# ECU_Dummy.net
KiCad netlist of a schematic drawn in Altium Designer
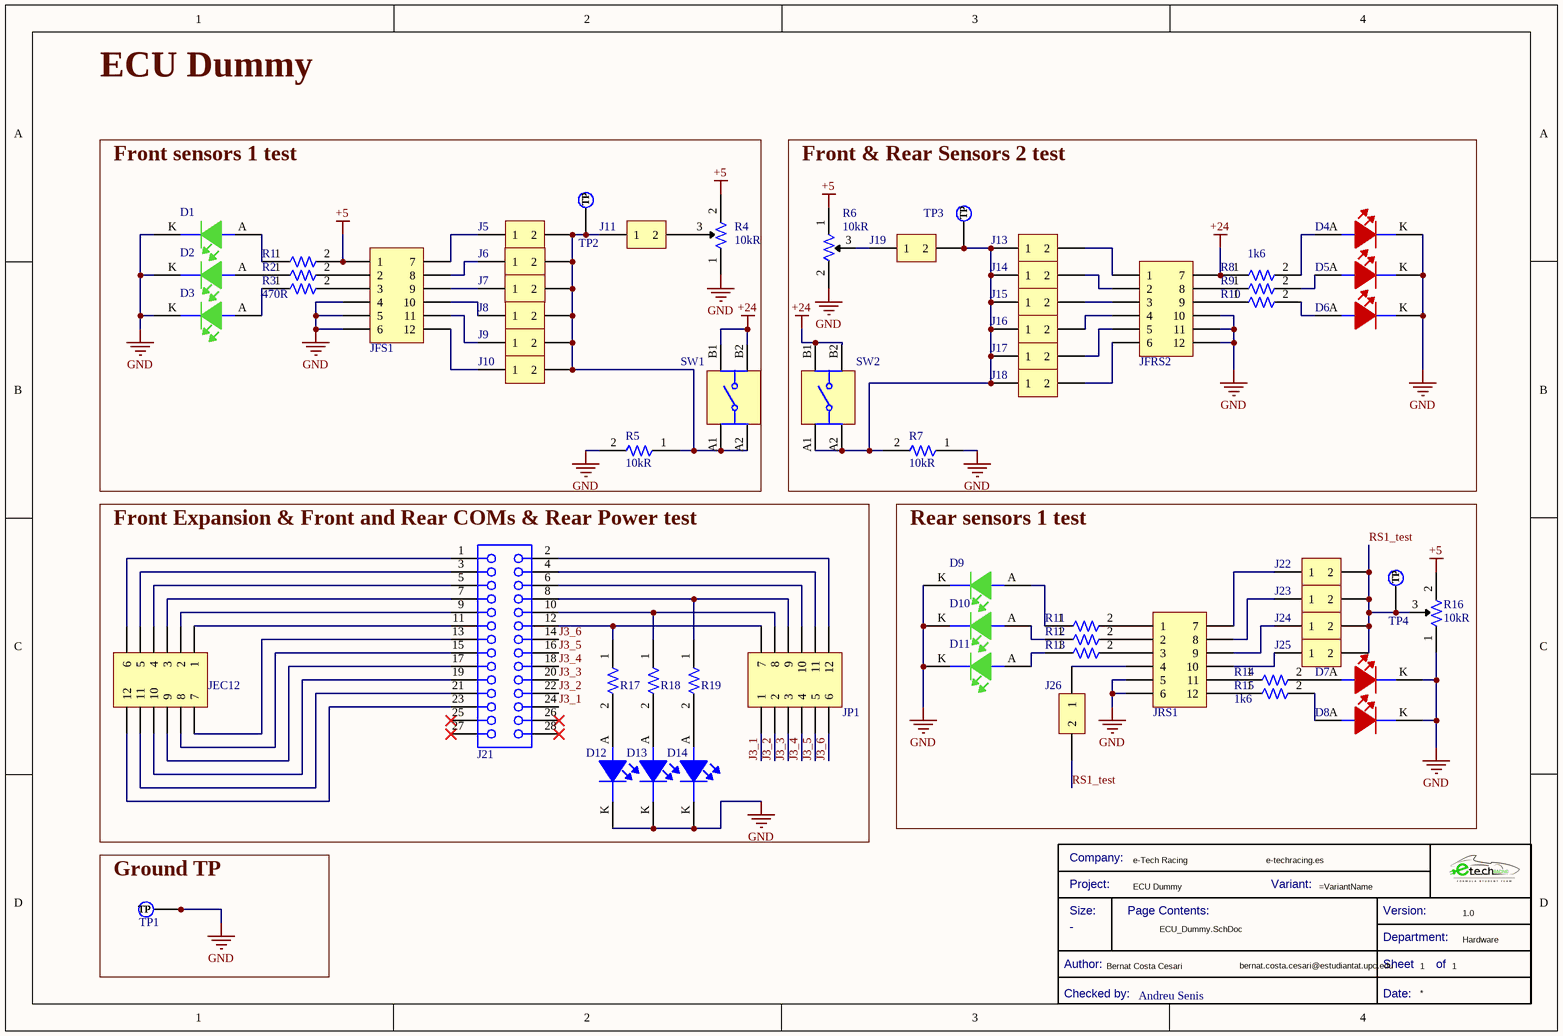
[diagram p0: ECU_Dummy.SchDoc]

(export (version "E")
  (design (tool "Eeschema 10.0.6"))
  (components
    (comp (ref "*")
      (value "Title Block_template")
      (description "Standard Title Block")
      (fields
        (field (name "SIZE") "-")
        (field (name ".CREATOR") "GP")
        (field (name ".PCBCHECK") "GP")
        (field (name ".SCHCHECK") "GP")
      )
      (libsource (lib "e-Tech_Racing") (part "Title Block_template"))
    )
    (comp (ref "D1")
      (value "150080GS75000")
      (footprint "LED_0805_WE")
      (description "Led, Green, 520 Nm, 3.2 V, 30 Ma, 450 Mcd Rohs Compliant: Yes")
      (fields (field (name ".CREATOR") "GP"))
      (libsource (lib "Semiconductor") (part "LEDGS-0805-450"))
    )
    (comp (ref "D2")
      (value "150080GS75000")
      (footprint "LED_0805_WE")
      (description "Led, Green, 520 Nm, 3.2 V, 30 Ma, 450 Mcd Rohs Compliant: Yes")
      (fields (field (name ".CREATOR") "GP"))
      (libsource (lib "Semiconductor") (part "LEDGS-0805-450"))
    )
    (comp (ref "D3")
      (value "150080GS75000")
      (footprint "LED_0805_WE")
      (description "Led, Green, 520 Nm, 3.2 V, 30 Ma, 450 Mcd Rohs Compliant: Yes")
      (fields (field (name ".CREATOR") "GP"))
      (libsource (lib "Semiconductor") (part "LEDGS-0805-450"))
    )
    (comp (ref "D4")
      (value "150080RS75000")
      (footprint "LED_0805_WE")
      (description "0805(H=0.8mm) 红色 高亮 λD=625nm VF=2V IF=30mA PD=72mW")
      (fields (field (name ".CREATOR") "DR"))
      (libsource (lib "Semiconductor") (part "LEDRS-0805-150"))
    )
    (comp (ref "D5")
      (value "150080RS75000")
      (footprint "LED_0805_WE")
      (description "0805(H=0.8mm) 红色 高亮 λD=625nm VF=2V IF=30mA PD=72mW")
      (fields (field (name ".CREATOR") "DR"))
      (libsource (lib "Semiconductor") (part "LEDRS-0805-150"))
    )
    (comp (ref "D6")
      (value "150080RS75000")
      (footprint "LED_0805_WE")
      (description "0805(H=0.8mm) 红色 高亮 λD=625nm VF=2V IF=30mA PD=72mW")
      (fields (field (name ".CREATOR") "DR"))
      (libsource (lib "Semiconductor") (part "LEDRS-0805-150"))
    )
    (comp (ref "D7")
      (value "150080RS75000")
      (footprint "LED_0805_WE")
      (description "0805(H=0.8mm) 红色 高亮 λD=625nm VF=2V IF=30mA PD=72mW")
      (fields (field (name ".CREATOR") "DR"))
      (libsource (lib "Semiconductor") (part "LEDRS-0805-150"))
    )
    (comp (ref "D8")
      (value "150080RS75000")
      (footprint "LED_0805_WE")
      (description "0805(H=0.8mm) 红色 高亮 λD=625nm VF=2V IF=30mA PD=72mW")
      (fields (field (name ".CREATOR") "DR"))
      (libsource (lib "Semiconductor") (part "LEDRS-0805-150"))
    )
    (comp (ref "D9")
      (value "150080GS75000")
      (footprint "LED_0805_WE")
      (description "Led, Green, 520 Nm, 3.2 V, 30 Ma, 450 Mcd Rohs Compliant: Yes")
      (fields (field (name ".CREATOR") "GP"))
      (libsource (lib "Semiconductor") (part "LEDGS-0805-450"))
    )
    (comp (ref "D10")
      (value "150080GS75000")
      (footprint "LED_0805_WE")
      (description "Led, Green, 520 Nm, 3.2 V, 30 Ma, 450 Mcd Rohs Compliant: Yes")
      (fields (field (name ".CREATOR") "GP"))
      (libsource (lib "Semiconductor") (part "LEDGS-0805-450"))
    )
    (comp (ref "D11")
      (value "150080GS75000")
      (footprint "LED_0805_WE")
      (description "Led, Green, 520 Nm, 3.2 V, 30 Ma, 450 Mcd Rohs Compliant: Yes")
      (fields (field (name ".CREATOR") "GP"))
      (libsource (lib "Semiconductor") (part "LEDGS-0805-450"))
    )
    (comp (ref "D12")
      (value "150080BS75000")
      (footprint "LED_0805_WE")
      (description "LED BLUE CLEAR 0805 SMD")
      (fields (field (name ".CREATOR") "GP"))
      (libsource (lib "Semiconductor") (part "LEDBS-0805-145"))
    )
    (comp (ref "D13")
      (value "150080BS75000")
      (footprint "LED_0805_WE")
      (description "LED BLUE CLEAR 0805 SMD")
      (fields (field (name ".CREATOR") "GP"))
      (libsource (lib "Semiconductor") (part "LEDBS-0805-145"))
    )
    (comp (ref "D14")
      (value "150080BS75000")
      (footprint "LED_0805_WE")
      (description "LED BLUE CLEAR 0805 SMD")
      (fields (field (name ".CREATOR") "GP"))
      (libsource (lib "Semiconductor") (part "LEDBS-0805-145"))
    )
    (comp (ref "J5")
      (value "2 Pin Header")
      (footprint "J_Pinheader_1x2")
      (libsource (lib "Electromechanical") (part "J_Jumper_H"))
    )
    (comp (ref "J6")
      (value "2 Pin Header")
      (footprint "J_Pinheader_1x2")
      (libsource (lib "") (part "J_Jumper_H_2"))
    )
    (comp (ref "J7")
      (value "2 Pin Header")
      (footprint "J_Pinheader_1x2")
      (libsource (lib "") (part "J_Jumper_H_2"))
    )
    (comp (ref "J8")
      (value "2 Pin Header")
      (footprint "J_Pinheader_1x2")
      (libsource (lib "Electromechanical") (part "J_Jumper_H"))
    )
    (comp (ref "J9")
      (value "2 Pin Header")
      (footprint "J_Pinheader_1x2")
      (libsource (lib "Electromechanical") (part "J_Jumper_H"))
    )
    (comp (ref "J10")
      (value "2 Pin Header")
      (footprint "J_Pinheader_1x2")
      (libsource (lib "Electromechanical") (part "J_Jumper_H"))
    )
    (comp (ref "J11")
      (value "2 Pin Header")
      (footprint "J_Pinheader_1x2")
      (libsource (lib "Electromechanical") (part "J_Jumper_H"))
    )
    (comp (ref "J13")
      (value "2 Pin Header")
      (footprint "J_Pinheader_1x2")
      (libsource (lib "Electromechanical") (part "J_Jumper_H"))
    )
    (comp (ref "J14")
      (value "2 Pin Header")
      (footprint "J_Pinheader_1x2")
      (libsource (lib "Electromechanical") (part "J_Jumper_H"))
    )
    (comp (ref "J15")
      (value "2 Pin Header")
      (footprint "J_Pinheader_1x2")
      (libsource (lib "Electromechanical") (part "J_Jumper_H"))
    )
    (comp (ref "J16")
      (value "2 Pin Header")
      (footprint "J_Pinheader_1x2")
      (libsource (lib "Electromechanical") (part "J_Jumper_H"))
    )
    (comp (ref "J17")
      (value "2 Pin Header")
      (footprint "J_Pinheader_1x2")
      (libsource (lib "Electromechanical") (part "J_Jumper_H"))
    )
    (comp (ref "J18")
      (value "2 Pin Header")
      (footprint "J_Pinheader_1x2")
      (libsource (lib "Electromechanical") (part "J_Jumper_H"))
    )
    (comp (ref "J19")
      (value "2 Pin Header")
      (footprint "J_Pinheader_1x2")
      (libsource (lib "Electromechanical") (part "J_Jumper_H"))
    )
    (comp (ref "J21")
      (value "61002821821")
      (footprint "61002821821")
      (description "WR-PHD Socket Header, SMT, Vertical, pitch 2.54mm, 2 Row, 28P")
      (fields (field (name "MANUFACTURER") "Wurth Elektronik"))
      (libsource (lib "Electromechanical") (part "61002821821"))
    )
    (comp (ref "J22")
      (value "2 Pin Header")
      (footprint "J_Pinheader_1x2")
      (libsource (lib "Electromechanical") (part "J_Jumper_H"))
    )
    (comp (ref "J23")
      (value "2 Pin Header")
      (footprint "J_Pinheader_1x2")
      (libsource (lib "Electromechanical") (part "J_Jumper_H"))
    )
    (comp (ref "J24")
      (value "2 Pin Header")
      (footprint "J_Pinheader_1x2")
      (libsource (lib "Electromechanical") (part "J_Jumper_H"))
    )
    (comp (ref "J25")
      (value "2 Pin Header")
      (footprint "J_Pinheader_1x2")
      (libsource (lib "Electromechanical") (part "J_Jumper_H"))
    )
    (comp (ref "J26")
      (value "2 Pin Header")
      (footprint "J_Pinheader_1x2")
      (libsource (lib "") (part "J_Jumper_H_1"))
    )
    (comp (ref "JEC12")
      (value "1053101112")
      (footprint "J_NanoFit_2x6_V")
      (libsource (lib "") (part "J_NanoFit_2x6_V_1"))
    )
    (comp (ref "JFRS2")
      (value "1053101112")
      (footprint "J_NanoFit_2x6_V")
      (libsource (lib "Electromechanical") (part "J_NanoFit_2x6_V"))
    )
    (comp (ref "JFS1")
      (value "1053101112")
      (footprint "J_NanoFit_2x6_V")
      (libsource (lib "Electromechanical") (part "J_NanoFit_2x6_V"))
    )
    (comp (ref "JP1")
      (value "1053101112")
      (footprint "J_NanoFit_2x6_V")
      (libsource (lib "") (part "J_NanoFit_2x6_V_2"))
    )
    (comp (ref "JRS1")
      (value "1053101112")
      (footprint "J_NanoFit_2x6_V")
      (libsource (lib "Electromechanical") (part "J_NanoFit_2x6_V"))
    )
    (comp (ref "R1")
      (value "CR0805-FX-4700GLF")
      (footprint "R0805FTK")
      (description "Res Thick Film 0805 470 Ohm 1% 1/8W ±100ppm/°C Molded SMD SMD Paper Tape on Plastic Reel")
      (fields (field (name "TOLERANCE") "1%") (field (name ".CREATOR") "DR"))
      (libsource (lib "Passives") (part "R470-0805FTK"))
    )
    (comp (ref "R2")
      (value "CR0805-FX-4700GLF")
      (footprint "R0805FTK")
      (description "Res Thick Film 0805 470 Ohm 1% 1/8W ±100ppm/°C Molded SMD SMD Paper Tape on Plastic Reel")
      (fields (field (name "TOLERANCE") "1%") (field (name ".CREATOR") "DR"))
      (libsource (lib "Passives") (part "R470-0805FTK"))
    )
    (comp (ref "R3")
      (value "CR0805-FX-4700GLF")
      (footprint "R0805FTK")
      (description "Res Thick Film 0805 470 Ohm 1% 1/8W ±100ppm/°C Molded SMD SMD Paper Tape on Plastic Reel")
      (fields (field (name "TOLERANCE") "1%") (field (name ".CREATOR") "DR"))
      (libsource (lib "Passives") (part "R470-0805FTK"))
    )
    (comp (ref "R4")
      (value "3296W-1-103LF")
      (footprint "R10k-VTR")
      (description "Trimmer, Cermet, Rest 10 Kilohms, PCB, 25 Turns, Pwr-Rtg 0.5W, 3296 Series")
      (fields
        (field (name "MANUFACTURER") "Bourns")
        (field (name "TOLERANCE") "10%")
        (field (name "RESISTANCE") "10kR")
        (field (name ".CREATOR") "DO")
      )
      (libsource (lib "Passives") (part "R10k-VTR"))
    )
    (comp (ref "R5")
      (value "CR0805-JW-103ELF")
      (footprint "R0805FTK")
      (fields
        (field (name "TOLERANCE") "5%")
        (field (name "RESISTANCE") "10kR")
        (field (name ".CREATOR") "DR")
      )
      (libsource (lib "Passives") (part "R10k-0805FTK"))
    )
    (comp (ref "R6")
      (value "3296W-1-103LF")
      (footprint "R10k-VTR")
      (description "Trimmer, Cermet, Rest 10 Kilohms, PCB, 25 Turns, Pwr-Rtg 0.5W, 3296 Series")
      (fields
        (field (name "MANUFACTURER") "Bourns")
        (field (name "TOLERANCE") "10%")
        (field (name "RESISTANCE") "10kR")
        (field (name ".CREATOR") "DO")
      )
      (libsource (lib "Passives") (part "R10k-VTR"))
    )
    (comp (ref "R7")
      (value "CR0805-JW-103ELF")
      (footprint "R0805FTK")
      (fields
        (field (name "TOLERANCE") "5%")
        (field (name "RESISTANCE") "10kR")
        (field (name ".CREATOR") "DR")
      )
      (libsource (lib "Passives") (part "R10k-0805FTK"))
    )
    (comp (ref "R8")
      (value "CR1206-FX-2201ELF")
      (footprint "R1206FTK-W")
      (description "Res Thick Film 1206 2.2K Ohm 1% 1/4W ±100ppm/°C Molded SMD SMD Paper Tape on Plastic Reel")
      (fields (field (name "TOLERANCE") "1%") (field (name ".CREATOR") "AC"))
      (libsource (lib "Passives") (part "R2.2K-1206FTK"))
    )
    (comp (ref "R9")
      (value "CR1206-FX-2201ELF")
      (footprint "R1206FTK-W")
      (description "Res Thick Film 1206 2.2K Ohm 1% 1/4W ±100ppm/°C Molded SMD SMD Paper Tape on Plastic Reel")
      (fields (field (name "TOLERANCE") "1%") (field (name ".CREATOR") "AC"))
      (libsource (lib "Passives") (part "R2.2K-1206FTK"))
    )
    (comp (ref "R10")
      (value "CR1206-FX-2201ELF")
      (footprint "R1206FTK-W")
      (description "Res Thick Film 1206 2.2K Ohm 1% 1/4W ±100ppm/°C Molded SMD SMD Paper Tape on Plastic Reel")
      (fields (field (name "TOLERANCE") "1%") (field (name ".CREATOR") "AC"))
      (libsource (lib "Passives") (part "R2.2K-1206FTK"))
    )
    (comp (ref "R11")
      (value "CR0805-FX-4700GLF")
      (footprint "R0805FTK")
      (description "Res Thick Film 0805 470 Ohm 1% 1/8W ±100ppm/°C Molded SMD SMD Paper Tape on Plastic Reel")
      (fields (field (name "TOLERANCE") "1%") (field (name ".CREATOR") "DR"))
      (libsource (lib "Passives") (part "R470-0805FTK"))
    )
    (comp (ref "R12")
      (value "CR0805-FX-4700GLF")
      (footprint "R0805FTK")
      (description "Res Thick Film 0805 470 Ohm 1% 1/8W ±100ppm/°C Molded SMD SMD Paper Tape on Plastic Reel")
      (fields (field (name "TOLERANCE") "1%") (field (name ".CREATOR") "DR"))
      (libsource (lib "Passives") (part "R470-0805FTK"))
    )
    (comp (ref "R13")
      (value "CR0805-FX-4700GLF")
      (footprint "R0805FTK")
      (description "Res Thick Film 0805 470 Ohm 1% 1/8W ±100ppm/°C Molded SMD SMD Paper Tape on Plastic Reel")
      (fields (field (name "TOLERANCE") "1%") (field (name ".CREATOR") "DR"))
      (libsource (lib "Passives") (part "R470-0805FTK"))
    )
    (comp (ref "R14")
      (value "CR1206-FX-2201ELF")
      (footprint "R1206FTK-W")
      (description "Res Thick Film 1206 2.2K Ohm 1% 1/4W ±100ppm/°C Molded SMD SMD Paper Tape on Plastic Reel")
      (fields (field (name "TOLERANCE") "1%") (field (name ".CREATOR") "AC"))
      (libsource (lib "Passives") (part "R2.2K-1206FTK"))
    )
    (comp (ref "R15")
      (value "CR1206-FX-2201ELF")
      (footprint "R1206FTK-W")
      (description "Res Thick Film 1206 2.2K Ohm 1% 1/4W ±100ppm/°C Molded SMD SMD Paper Tape on Plastic Reel")
      (fields (field (name "TOLERANCE") "1%") (field (name ".CREATOR") "AC"))
      (libsource (lib "Passives") (part "R2.2K-1206FTK"))
    )
    (comp (ref "R16")
      (value "3296W-1-103LF")
      (footprint "R10k-VTR")
      (description "Trimmer, Cermet, Rest 10 Kilohms, PCB, 25 Turns, Pwr-Rtg 0.5W, 3296 Series")
      (fields
        (field (name "MANUFACTURER") "Bourns")
        (field (name "TOLERANCE") "10%")
        (field (name "RESISTANCE") "10kR")
        (field (name ".CREATOR") "DO")
      )
      (libsource (lib "Passives") (part "R10k-VTR"))
    )
    (comp (ref "R17")
      (value "CR0805-FX-4700GLF")
      (footprint "R0805FTK")
      (description "Res Thick Film 0805 470 Ohm 1% 1/8W ±100ppm/°C Molded SMD SMD Paper Tape on Plastic Reel")
      (fields (field (name "TOLERANCE") "1%") (field (name ".CREATOR") "DR"))
      (libsource (lib "Passives") (part "R470-0805FTK"))
    )
    (comp (ref "R18")
      (value "CR0805-FX-4700GLF")
      (footprint "R0805FTK")
      (description "Res Thick Film 0805 470 Ohm 1% 1/8W ±100ppm/°C Molded SMD SMD Paper Tape on Plastic Reel")
      (fields (field (name "TOLERANCE") "1%") (field (name ".CREATOR") "DR"))
      (libsource (lib "Passives") (part "R470-0805FTK"))
    )
    (comp (ref "R19")
      (value "CR0805-FX-4700GLF")
      (footprint "R0805FTK")
      (description "Res Thick Film 0805 470 Ohm 1% 1/8W ±100ppm/°C Molded SMD SMD Paper Tape on Plastic Reel")
      (fields (field (name "TOLERANCE") "1%") (field (name ".CREATOR") "DR"))
      (libsource (lib "Passives") (part "R470-0805FTK"))
    )
    (comp (ref "SW1")
      (value "430773034825")
      (footprint "WS-TASV_L6W6H3.4_4307x30348xx")
      (description "WS-TASV J-Hook SMT Hermetic Tact Switch, L6 x W6 x H3.4mm, 250g, SPST-NO, 12V, 50mA")
      (fields (field (name "MANUFACTURER") "Wurth Elektronik"))
      (libsource (lib "Electromechanical") (part "430773034825"))
    )
    (comp (ref "SW2")
      (value "430773034825")
      (footprint "WS-TASV_L6W6H3.4_4307x30348xx")
      (description "WS-TASV J-Hook SMT Hermetic Tact Switch, L6 x W6 x H3.4mm, 250g, SPST-NO, 12V, 50mA")
      (fields (field (name "MANUFACTURER") "Wurth Elektronik"))
      (libsource (lib "Electromechanical") (part "430773034825"))
    )
    (comp (ref "TP1")
      (value "Test Point")
      (footprint "TESTPOINT_WIDE")
      (description "TestPoint 5x5mm")
      (libsource (lib "e-Tech_Racing") (part "TestPoint_Wide"))
    )
    (comp (ref "TP2")
      (value "TestPoint")
      (footprint "TestPoint")
      (description "Test Point 1x1 mm")
      (fields (field (name ".CREATOR") "GP") (field (name ".PCBCHECK") "GP") (field (name ".SCHCHECK") "GP"))
      (libsource (lib "e-Tech_Racing") (part "TestPoint"))
    )
    (comp (ref "TP3")
      (value "TestPoint")
      (footprint "TestPoint")
      (description "Test Point 1x1 mm")
      (fields (field (name ".CREATOR") "GP") (field (name ".PCBCHECK") "GP") (field (name ".SCHCHECK") "GP"))
      (libsource (lib "e-Tech_Racing") (part "TestPoint"))
    )
    (comp (ref "TP4")
      (value "TestPoint")
      (footprint "TestPoint")
      (description "Test Point 1x1 mm")
      (fields (field (name ".CREATOR") "GP") (field (name ".PCBCHECK") "GP") (field (name ".SCHCHECK") "GP"))
      (libsource (lib "e-Tech_Racing") (part "TestPoint"))
    )
  )
  (nets
    (net (code "1") (name "+5") (class "Default")
      (node (ref "JFS1") (pin "1") (pinfunction "1_1") (pintype "passive"))
      (node (ref "R1") (pin "2") (pinfunction "2_2") (pintype "passive"))
      (node (ref "R16") (pin "2") (pinfunction "2_2") (pintype "passive"))
      (node (ref "R4") (pin "2") (pinfunction "2_2") (pintype "passive"))
      (node (ref "R6") (pin "1") (pinfunction "2_1") (pintype "passive"))
    )
    (net (code "2") (name "+24") (class "Default")
      (node (ref "JFRS2") (pin "7") (pinfunction "7_7") (pintype "passive"))
      (node (ref "R8") (pin "1") (pinfunction "1_1") (pintype "passive"))
      (node (ref "SW1") (pin "B1") (pinfunction "B1_B1") (pintype "passive"))
      (node (ref "SW1") (pin "B2") (pinfunction "B2_B2") (pintype "passive"))
      (node (ref "SW2") (pin "B1") (pinfunction "B1_B1") (pintype "passive"))
      (node (ref "SW2") (pin "B2") (pinfunction "B2_B2") (pintype "passive"))
    )
    (net (code "3") (name "/J3_1") (class "Default")
      (node (ref "J21") (pin "24") (pinfunction "24_24") (pintype "passive"))
      (node (ref "JP1") (pin "1") (pinfunction "1_1") (pintype "passive"))
    )
    (net (code "4") (name "/J3_2") (class "Default")
      (node (ref "J21") (pin "22") (pinfunction "22_22") (pintype "passive"))
      (node (ref "JP1") (pin "2") (pinfunction "2_2") (pintype "passive"))
    )
    (net (code "5") (name "/J3_3") (class "Default")
      (node (ref "J21") (pin "20") (pinfunction "20_20") (pintype "passive"))
      (node (ref "JP1") (pin "3") (pinfunction "3_3") (pintype "passive"))
    )
    (net (code "6") (name "/J3_4") (class "Default")
      (node (ref "J21") (pin "18") (pinfunction "18_18") (pintype "passive"))
      (node (ref "JP1") (pin "4") (pinfunction "4_4") (pintype "passive"))
    )
    (net (code "7") (name "/J3_5") (class "Default")
      (node (ref "J21") (pin "16") (pinfunction "16_16") (pintype "passive"))
      (node (ref "JP1") (pin "5") (pinfunction "5_5") (pintype "passive"))
    )
    (net (code "8") (name "/J3_6") (class "Default")
      (node (ref "J21") (pin "14") (pinfunction "14_14") (pintype "passive"))
      (node (ref "JP1") (pin "6") (pinfunction "6_6") (pintype "passive"))
    )
    (net (code "9") (name "/RS1_test") (class "Default")
      (node (ref "J22") (pin "2") (pinfunction "2_2") (pintype "passive"))
      (node (ref "J23") (pin "2") (pinfunction "2_2") (pintype "passive"))
      (node (ref "J24") (pin "2") (pinfunction "2_2") (pintype "passive"))
      (node (ref "J25") (pin "2") (pinfunction "2_2") (pintype "passive"))
      (node (ref "J26") (pin "2") (pinfunction "2_2") (pintype "passive"))
      (node (ref "R16") (pin "3") (pinfunction "3_3") (pintype "passive"))
      (node (ref "TP4") (pin "1") (pinfunction "TP_1") (pintype "passive"))
    )
    (net (code "10") (name "GND") (class "Default")
      (node (ref "D1") (pin "K") (pinfunction "K_K") (pintype "passive"))
      (node (ref "D10") (pin "K") (pinfunction "K_K") (pintype "passive"))
      (node (ref "D11") (pin "K") (pinfunction "K_K") (pintype "passive"))
      (node (ref "D12") (pin "K") (pinfunction "K_K") (pintype "passive"))
      (node (ref "D13") (pin "K") (pinfunction "K_K") (pintype "passive"))
      (node (ref "D14") (pin "K") (pinfunction "K_K") (pintype "passive"))
      (node (ref "D2") (pin "K") (pinfunction "K_K") (pintype "passive"))
      (node (ref "D3") (pin "K") (pinfunction "K_K") (pintype "passive"))
      (node (ref "D4") (pin "K") (pinfunction "K_K") (pintype "passive"))
      (node (ref "D5") (pin "K") (pinfunction "K_K") (pintype "passive"))
      (node (ref "D6") (pin "K") (pinfunction "K_K") (pintype "passive"))
      (node (ref "D7") (pin "K") (pinfunction "K_K") (pintype "passive"))
      (node (ref "D8") (pin "K") (pinfunction "K_K") (pintype "passive"))
      (node (ref "D9") (pin "K") (pinfunction "K_K") (pintype "passive"))
      (node (ref "JFRS2") (pin "10") (pinfunction "10_10") (pintype "passive"))
      (node (ref "JFRS2") (pin "11") (pinfunction "11_11") (pintype "passive"))
      (node (ref "JFRS2") (pin "12") (pinfunction "12_12") (pintype "passive"))
      (node (ref "JFS1") (pin "4") (pinfunction "4_4") (pintype "passive"))
      (node (ref "JFS1") (pin "5") (pinfunction "5_5") (pintype "passive"))
      (node (ref "JFS1") (pin "6") (pinfunction "6_6") (pintype "passive"))
      (node (ref "JRS1") (pin "5") (pinfunction "5_5") (pintype "passive"))
      (node (ref "JRS1") (pin "6") (pinfunction "6_6") (pintype "passive"))
      (node (ref "R16") (pin "1") (pinfunction "2_1") (pintype "passive"))
      (node (ref "R4") (pin "1") (pinfunction "2_1") (pintype "passive"))
      (node (ref "R5") (pin "2") (pinfunction "2_2") (pintype "passive"))
      (node (ref "R6") (pin "2") (pinfunction "2_2") (pintype "passive"))
      (node (ref "R7") (pin "1") (pinfunction "1_1") (pintype "passive"))
      (node (ref "TP1") (pin "1") (pinfunction "TP_1") (pintype "passive"))
    )
    (net (code "11") (name "Net-(D1-PadA)") (class "Default")
      (node (ref "D1") (pin "A") (pinfunction "A_A") (pintype "passive"))
      (node (ref "R1") (pin "1") (pinfunction "1_1") (pintype "passive"))
    )
    (net (code "12") (name "Net-(D2-PadA)") (class "Default")
      (node (ref "D2") (pin "A") (pinfunction "A_A") (pintype "passive"))
      (node (ref "R2") (pin "1") (pinfunction "1_1") (pintype "passive"))
    )
    (net (code "13") (name "Net-(D3-PadA)") (class "Default")
      (node (ref "D3") (pin "A") (pinfunction "A_A") (pintype "passive"))
      (node (ref "R3") (pin "1") (pinfunction "1_1") (pintype "passive"))
    )
    (net (code "14") (name "Net-(D4-PadA)") (class "Default")
      (node (ref "D4") (pin "A") (pinfunction "A_A") (pintype "passive"))
      (node (ref "R8") (pin "2") (pinfunction "2_2") (pintype "passive"))
    )
    (net (code "15") (name "Net-(D5-PadA)") (class "Default")
      (node (ref "D5") (pin "A") (pinfunction "A_A") (pintype "passive"))
      (node (ref "R9") (pin "2") (pinfunction "2_2") (pintype "passive"))
    )
    (net (code "16") (name "Net-(D6-PadA)") (class "Default")
      (node (ref "D6") (pin "A") (pinfunction "A_A") (pintype "passive"))
      (node (ref "R10") (pin "2") (pinfunction "2_2") (pintype "passive"))
    )
    (net (code "17") (name "Net-(D7-PadA)") (class "Default")
      (node (ref "D7") (pin "A") (pinfunction "A_A") (pintype "passive"))
      (node (ref "R14") (pin "2") (pinfunction "2_2") (pintype "passive"))
    )
    (net (code "18") (name "Net-(D8-PadA)") (class "Default")
      (node (ref "D8") (pin "A") (pinfunction "A_A") (pintype "passive"))
      (node (ref "R15") (pin "2") (pinfunction "2_2") (pintype "passive"))
    )
    (net (code "19") (name "Net-(D9-PadA)") (class "Default")
      (node (ref "D9") (pin "A") (pinfunction "A_A") (pintype "passive"))
      (node (ref "R11") (pin "1") (pinfunction "1_1") (pintype "passive"))
    )
    (net (code "20") (name "Net-(D10-PadA)") (class "Default")
      (node (ref "D10") (pin "A") (pinfunction "A_A") (pintype "passive"))
      (node (ref "R12") (pin "1") (pinfunction "1_1") (pintype "passive"))
    )
    (net (code "21") (name "Net-(D11-PadA)") (class "Default")
      (node (ref "D11") (pin "A") (pinfunction "A_A") (pintype "passive"))
      (node (ref "R13") (pin "1") (pinfunction "1_1") (pintype "passive"))
    )
    (net (code "22") (name "Net-(D12-PadA)") (class "Default")
      (node (ref "D12") (pin "A") (pinfunction "A_A") (pintype "passive"))
      (node (ref "R17") (pin "2") (pinfunction "2_2") (pintype "passive"))
    )
    (net (code "23") (name "Net-(D13-PadA)") (class "Default")
      (node (ref "D13") (pin "A") (pinfunction "A_A") (pintype "passive"))
      (node (ref "R18") (pin "2") (pinfunction "2_2") (pintype "passive"))
    )
    (net (code "24") (name "Net-(D14-PadA)") (class "Default")
      (node (ref "D14") (pin "A") (pinfunction "A_A") (pintype "passive"))
      (node (ref "R19") (pin "2") (pinfunction "2_2") (pintype "passive"))
    )
    (net (code "25") (name "Net-(J5-Pad1)") (class "Default")
      (node (ref "J5") (pin "1") (pinfunction "1_1") (pintype "passive"))
      (node (ref "JFS1") (pin "7") (pinfunction "7_7") (pintype "passive"))
    )
    (net (code "26") (name "Net-(J6-Pad1)") (class "Default")
      (node (ref "J6") (pin "1") (pinfunction "1_1") (pintype "passive"))
      (node (ref "JFS1") (pin "8") (pinfunction "8_8") (pintype "passive"))
    )
    (net (code "27") (name "Net-(J7-Pad1)") (class "Default")
      (node (ref "J7") (pin "1") (pinfunction "1_1") (pintype "passive"))
      (node (ref "JFS1") (pin "9") (pinfunction "9_9") (pintype "passive"))
    )
    (net (code "28") (name "Net-(J8-Pad1)") (class "Default")
      (node (ref "J8") (pin "1") (pinfunction "1_1") (pintype "passive"))
      (node (ref "JFS1") (pin "10") (pinfunction "10_10") (pintype "passive"))
    )
    (net (code "29") (name "Net-(J9-Pad1)") (class "Default")
      (node (ref "J9") (pin "1") (pinfunction "1_1") (pintype "passive"))
      (node (ref "JFS1") (pin "11") (pinfunction "11_11") (pintype "passive"))
    )
    (net (code "30") (name "Net-(J10-Pad1)") (class "Default")
      (node (ref "J10") (pin "1") (pinfunction "1_1") (pintype "passive"))
      (node (ref "JFS1") (pin "12") (pinfunction "12_12") (pintype "passive"))
    )
    (net (code "31") (name "Net-(J11-Pad2)") (class "Default")
      (node (ref "J11") (pin "2") (pinfunction "2_2") (pintype "passive"))
      (node (ref "R4") (pin "3") (pinfunction "3_3") (pintype "passive"))
    )
    (net (code "32") (name "Net-(J13-Pad2)") (class "Default")
      (node (ref "J13") (pin "2") (pinfunction "2_2") (pintype "passive"))
      (node (ref "JFRS2") (pin "1") (pinfunction "1_1") (pintype "passive"))
    )
    (net (code "33") (name "Net-(J14-Pad2)") (class "Default")
      (node (ref "J14") (pin "2") (pinfunction "2_2") (pintype "passive"))
      (node (ref "JFRS2") (pin "2") (pinfunction "2_2") (pintype "passive"))
    )
    (net (code "34") (name "Net-(J15-Pad2)") (class "Default")
      (node (ref "J15") (pin "2") (pinfunction "2_2") (pintype "passive"))
      (node (ref "JFRS2") (pin "3") (pinfunction "3_3") (pintype "passive"))
    )
    (net (code "35") (name "Net-(J16-Pad2)") (class "Default")
      (node (ref "J16") (pin "2") (pinfunction "2_2") (pintype "passive"))
      (node (ref "JFRS2") (pin "4") (pinfunction "4_4") (pintype "passive"))
    )
    (net (code "36") (name "Net-(J17-Pad2)") (class "Default")
      (node (ref "J17") (pin "2") (pinfunction "2_2") (pintype "passive"))
      (node (ref "JFRS2") (pin "5") (pinfunction "5_5") (pintype "passive"))
    )
    (net (code "37") (name "Net-(J18-Pad2)") (class "Default")
      (node (ref "J18") (pin "2") (pinfunction "2_2") (pintype "passive"))
      (node (ref "JFRS2") (pin "6") (pinfunction "6_6") (pintype "passive"))
    )
    (net (code "38") (name "Net-(J19-Pad1)") (class "Default")
      (node (ref "J19") (pin "1") (pinfunction "1_1") (pintype "passive"))
      (node (ref "R6") (pin "3") (pinfunction "3_3") (pintype "passive"))
    )
    (net (code "39") (name "Net-(J21-Pad1)") (class "Default")
      (node (ref "J21") (pin "1") (pinfunction "1_1") (pintype "passive"))
      (node (ref "JEC12") (pin "6") (pinfunction "6_6") (pintype "passive"))
    )
    (net (code "40") (name "Net-(J21-Pad2)") (class "Default")
      (node (ref "J21") (pin "2") (pinfunction "2_2") (pintype "passive"))
      (node (ref "JP1") (pin "12") (pinfunction "12_12") (pintype "passive"))
    )
    (net (code "41") (name "Net-(J21-Pad3)") (class "Default")
      (node (ref "J21") (pin "3") (pinfunction "3_3") (pintype "passive"))
      (node (ref "JEC12") (pin "5") (pinfunction "5_5") (pintype "passive"))
    )
    (net (code "42") (name "Net-(J21-Pad4)") (class "Default")
      (node (ref "J21") (pin "4") (pinfunction "4_4") (pintype "passive"))
      (node (ref "JP1") (pin "11") (pinfunction "11_11") (pintype "passive"))
    )
    (net (code "43") (name "Net-(J21-Pad5)") (class "Default")
      (node (ref "J21") (pin "5") (pinfunction "5_5") (pintype "passive"))
      (node (ref "JEC12") (pin "4") (pinfunction "4_4") (pintype "passive"))
    )
    (net (code "44") (name "Net-(J21-Pad6)") (class "Default")
      (node (ref "J21") (pin "6") (pinfunction "6_6") (pintype "passive"))
      (node (ref "JP1") (pin "10") (pinfunction "10_10") (pintype "passive"))
    )
    (net (code "45") (name "Net-(J21-Pad7)") (class "Default")
      (node (ref "J21") (pin "7") (pinfunction "7_7") (pintype "passive"))
      (node (ref "JEC12") (pin "3") (pinfunction "3_3") (pintype "passive"))
    )
    (net (code "46") (name "Net-(J21-Pad8)") (class "Default")
      (node (ref "J21") (pin "8") (pinfunction "8_8") (pintype "passive"))
      (node (ref "JP1") (pin "9") (pinfunction "9_9") (pintype "passive"))
      (node (ref "R19") (pin "1") (pinfunction "1_1") (pintype "passive"))
    )
    (net (code "47") (name "Net-(J21-Pad9)") (class "Default")
      (node (ref "J21") (pin "9") (pinfunction "9_9") (pintype "passive"))
      (node (ref "JEC12") (pin "2") (pinfunction "2_2") (pintype "passive"))
    )
    (net (code "48") (name "Net-(J21-Pad10)") (class "Default")
      (node (ref "J21") (pin "10") (pinfunction "10_10") (pintype "passive"))
      (node (ref "JP1") (pin "8") (pinfunction "8_8") (pintype "passive"))
      (node (ref "R18") (pin "1") (pinfunction "1_1") (pintype "passive"))
    )
    (net (code "49") (name "Net-(J21-Pad11)") (class "Default")
      (node (ref "J21") (pin "11") (pinfunction "11_11") (pintype "passive"))
      (node (ref "JEC12") (pin "1") (pinfunction "1_1") (pintype "passive"))
    )
    (net (code "50") (name "Net-(J21-Pad12)") (class "Default")
      (node (ref "J21") (pin "12") (pinfunction "12_12") (pintype "passive"))
      (node (ref "JP1") (pin "7") (pinfunction "7_7") (pintype "passive"))
      (node (ref "R17") (pin "1") (pinfunction "1_1") (pintype "passive"))
    )
    (net (code "51") (name "Net-(J21-Pad13)") (class "Default")
      (node (ref "J21") (pin "13") (pinfunction "13_13") (pintype "passive"))
      (node (ref "JEC12") (pin "7") (pinfunction "7_7") (pintype "passive"))
    )
    (net (code "52") (name "Net-(J21-Pad15)") (class "Default")
      (node (ref "J21") (pin "15") (pinfunction "15_15") (pintype "passive"))
      (node (ref "JEC12") (pin "8") (pinfunction "8_8") (pintype "passive"))
    )
    (net (code "53") (name "Net-(J21-Pad17)") (class "Default")
      (node (ref "J21") (pin "17") (pinfunction "17_17") (pintype "passive"))
      (node (ref "JEC12") (pin "9") (pinfunction "9_9") (pintype "passive"))
    )
    (net (code "54") (name "Net-(J21-Pad19)") (class "Default")
      (node (ref "J21") (pin "19") (pinfunction "19_19") (pintype "passive"))
      (node (ref "JEC12") (pin "10") (pinfunction "10_10") (pintype "passive"))
    )
    (net (code "55") (name "Net-(J21-Pad21)") (class "Default")
      (node (ref "J21") (pin "21") (pinfunction "21_21") (pintype "passive"))
      (node (ref "JEC12") (pin "11") (pinfunction "11_11") (pintype "passive"))
    )
    (net (code "56") (name "Net-(J21-Pad23)") (class "Default")
      (node (ref "J21") (pin "23") (pinfunction "23_23") (pintype "passive"))
      (node (ref "JEC12") (pin "12") (pinfunction "12_12") (pintype "passive"))
    )
    (net (code "57") (name "Net-(J22-Pad1)") (class "Default")
      (node (ref "J22") (pin "1") (pinfunction "1_1") (pintype "passive"))
      (node (ref "JRS1") (pin "7") (pinfunction "7_7") (pintype "passive"))
    )
    (net (code "58") (name "Net-(J23-Pad1)") (class "Default")
      (node (ref "J23") (pin "1") (pinfunction "1_1") (pintype "passive"))
      (node (ref "JRS1") (pin "8") (pinfunction "8_8") (pintype "passive"))
    )
    (net (code "59") (name "Net-(J24-Pad1)") (class "Default")
      (node (ref "J24") (pin "1") (pinfunction "1_1") (pintype "passive"))
      (node (ref "JRS1") (pin "9") (pinfunction "9_9") (pintype "passive"))
    )
    (net (code "60") (name "Net-(J25-Pad1)") (class "Default")
      (node (ref "J25") (pin "1") (pinfunction "1_1") (pintype "passive"))
      (node (ref "JRS1") (pin "10") (pinfunction "10_10") (pintype "passive"))
    )
    (net (code "61") (name "Net-(J26-Pad1)") (class "Default")
      (node (ref "J26") (pin "1") (pinfunction "1_1") (pintype "passive"))
      (node (ref "JRS1") (pin "4") (pinfunction "4_4") (pintype "passive"))
    )
    (net (code "62") (name "Net-(JFRS2-Pad8)") (class "Default")
      (node (ref "JFRS2") (pin "8") (pinfunction "8_8") (pintype "passive"))
      (node (ref "R9") (pin "1") (pinfunction "1_1") (pintype "passive"))
    )
    (net (code "63") (name "Net-(JFRS2-Pad9)") (class "Default")
      (node (ref "JFRS2") (pin "9") (pinfunction "9_9") (pintype "passive"))
      (node (ref "R10") (pin "1") (pinfunction "1_1") (pintype "passive"))
    )
    (net (code "64") (name "Net-(JFS1-Pad2)") (class "Default")
      (node (ref "JFS1") (pin "2") (pinfunction "2_2") (pintype "passive"))
      (node (ref "R2") (pin "2") (pinfunction "2_2") (pintype "passive"))
    )
    (net (code "65") (name "Net-(JFS1-Pad3)") (class "Default")
      (node (ref "JFS1") (pin "3") (pinfunction "3_3") (pintype "passive"))
      (node (ref "R3") (pin "2") (pinfunction "2_2") (pintype "passive"))
    )
    (net (code "66") (name "Net-(JRS1-Pad1)") (class "Default")
      (node (ref "JRS1") (pin "1") (pinfunction "1_1") (pintype "passive"))
      (node (ref "R11") (pin "2") (pinfunction "2_2") (pintype "passive"))
    )
    (net (code "67") (name "Net-(JRS1-Pad2)") (class "Default")
      (node (ref "JRS1") (pin "2") (pinfunction "2_2") (pintype "passive"))
      (node (ref "R12") (pin "2") (pinfunction "2_2") (pintype "passive"))
    )
    (net (code "68") (name "Net-(JRS1-Pad3)") (class "Default")
      (node (ref "JRS1") (pin "3") (pinfunction "3_3") (pintype "passive"))
      (node (ref "R13") (pin "2") (pinfunction "2_2") (pintype "passive"))
    )
    (net (code "69") (name "Net-(JRS1-Pad11)") (class "Default")
      (node (ref "JRS1") (pin "11") (pinfunction "11_11") (pintype "passive"))
      (node (ref "R14") (pin "1") (pinfunction "1_1") (pintype "passive"))
    )
    (net (code "70") (name "Net-(JRS1-Pad12)") (class "Default")
      (node (ref "JRS1") (pin "12") (pinfunction "12_12") (pintype "passive"))
      (node (ref "R15") (pin "1") (pinfunction "1_1") (pintype "passive"))
    )
    (net (code "71") (name "Net-(TP2-TP)") (class "Default")
      (node (ref "J10") (pin "2") (pinfunction "2_2") (pintype "passive"))
      (node (ref "J11") (pin "1") (pinfunction "1_1") (pintype "passive"))
      (node (ref "J5") (pin "2") (pinfunction "2_2") (pintype "passive"))
      (node (ref "J6") (pin "2") (pinfunction "2_2") (pintype "passive"))
      (node (ref "J7") (pin "2") (pinfunction "2_2") (pintype "passive"))
      (node (ref "J8") (pin "2") (pinfunction "2_2") (pintype "passive"))
      (node (ref "J9") (pin "2") (pinfunction "2_2") (pintype "passive"))
      (node (ref "R5") (pin "1") (pinfunction "1_1") (pintype "passive"))
      (node (ref "SW1") (pin "A1") (pinfunction "A1_A1") (pintype "passive"))
      (node (ref "SW1") (pin "A2") (pinfunction "A2_A2") (pintype "passive"))
      (node (ref "TP2") (pin "1") (pinfunction "TP_1") (pintype "passive"))
    )
    (net (code "72") (name "Net-(TP3-TP)") (class "Default")
      (node (ref "J13") (pin "1") (pinfunction "1_1") (pintype "passive"))
      (node (ref "J14") (pin "1") (pinfunction "1_1") (pintype "passive"))
      (node (ref "J15") (pin "1") (pinfunction "1_1") (pintype "passive"))
      (node (ref "J16") (pin "1") (pinfunction "1_1") (pintype "passive"))
      (node (ref "J17") (pin "1") (pinfunction "1_1") (pintype "passive"))
      (node (ref "J18") (pin "1") (pinfunction "1_1") (pintype "passive"))
      (node (ref "J19") (pin "2") (pinfunction "2_2") (pintype "passive"))
      (node (ref "R7") (pin "2") (pinfunction "2_2") (pintype "passive"))
      (node (ref "SW2") (pin "A1") (pinfunction "A1_A1") (pintype "passive"))
      (node (ref "SW2") (pin "A2") (pinfunction "A2_A2") (pintype "passive"))
      (node (ref "TP3") (pin "1") (pinfunction "TP_1") (pintype "passive"))
    )
    (net (code "73") (name "unconnected-(J21-Pad25)") (class "Default")
      (node (ref "J21") (pin "25") (pinfunction "25_25") (pintype "passive+no_connect"))
    )
    (net (code "74") (name "unconnected-(J21-Pad26)") (class "Default")
      (node (ref "J21") (pin "26") (pinfunction "26_26") (pintype "passive+no_connect"))
    )
    (net (code "75") (name "unconnected-(J21-Pad27)") (class "Default")
      (node (ref "J21") (pin "27") (pinfunction "27_27") (pintype "passive+no_connect"))
    )
    (net (code "76") (name "unconnected-(J21-Pad28)") (class "Default")
      (node (ref "J21") (pin "28") (pinfunction "28_28") (pintype "passive+no_connect"))
    )
  )
)
